# FogCalBoard.net
KiCad netlist of a schematic drawn in Altium Designer
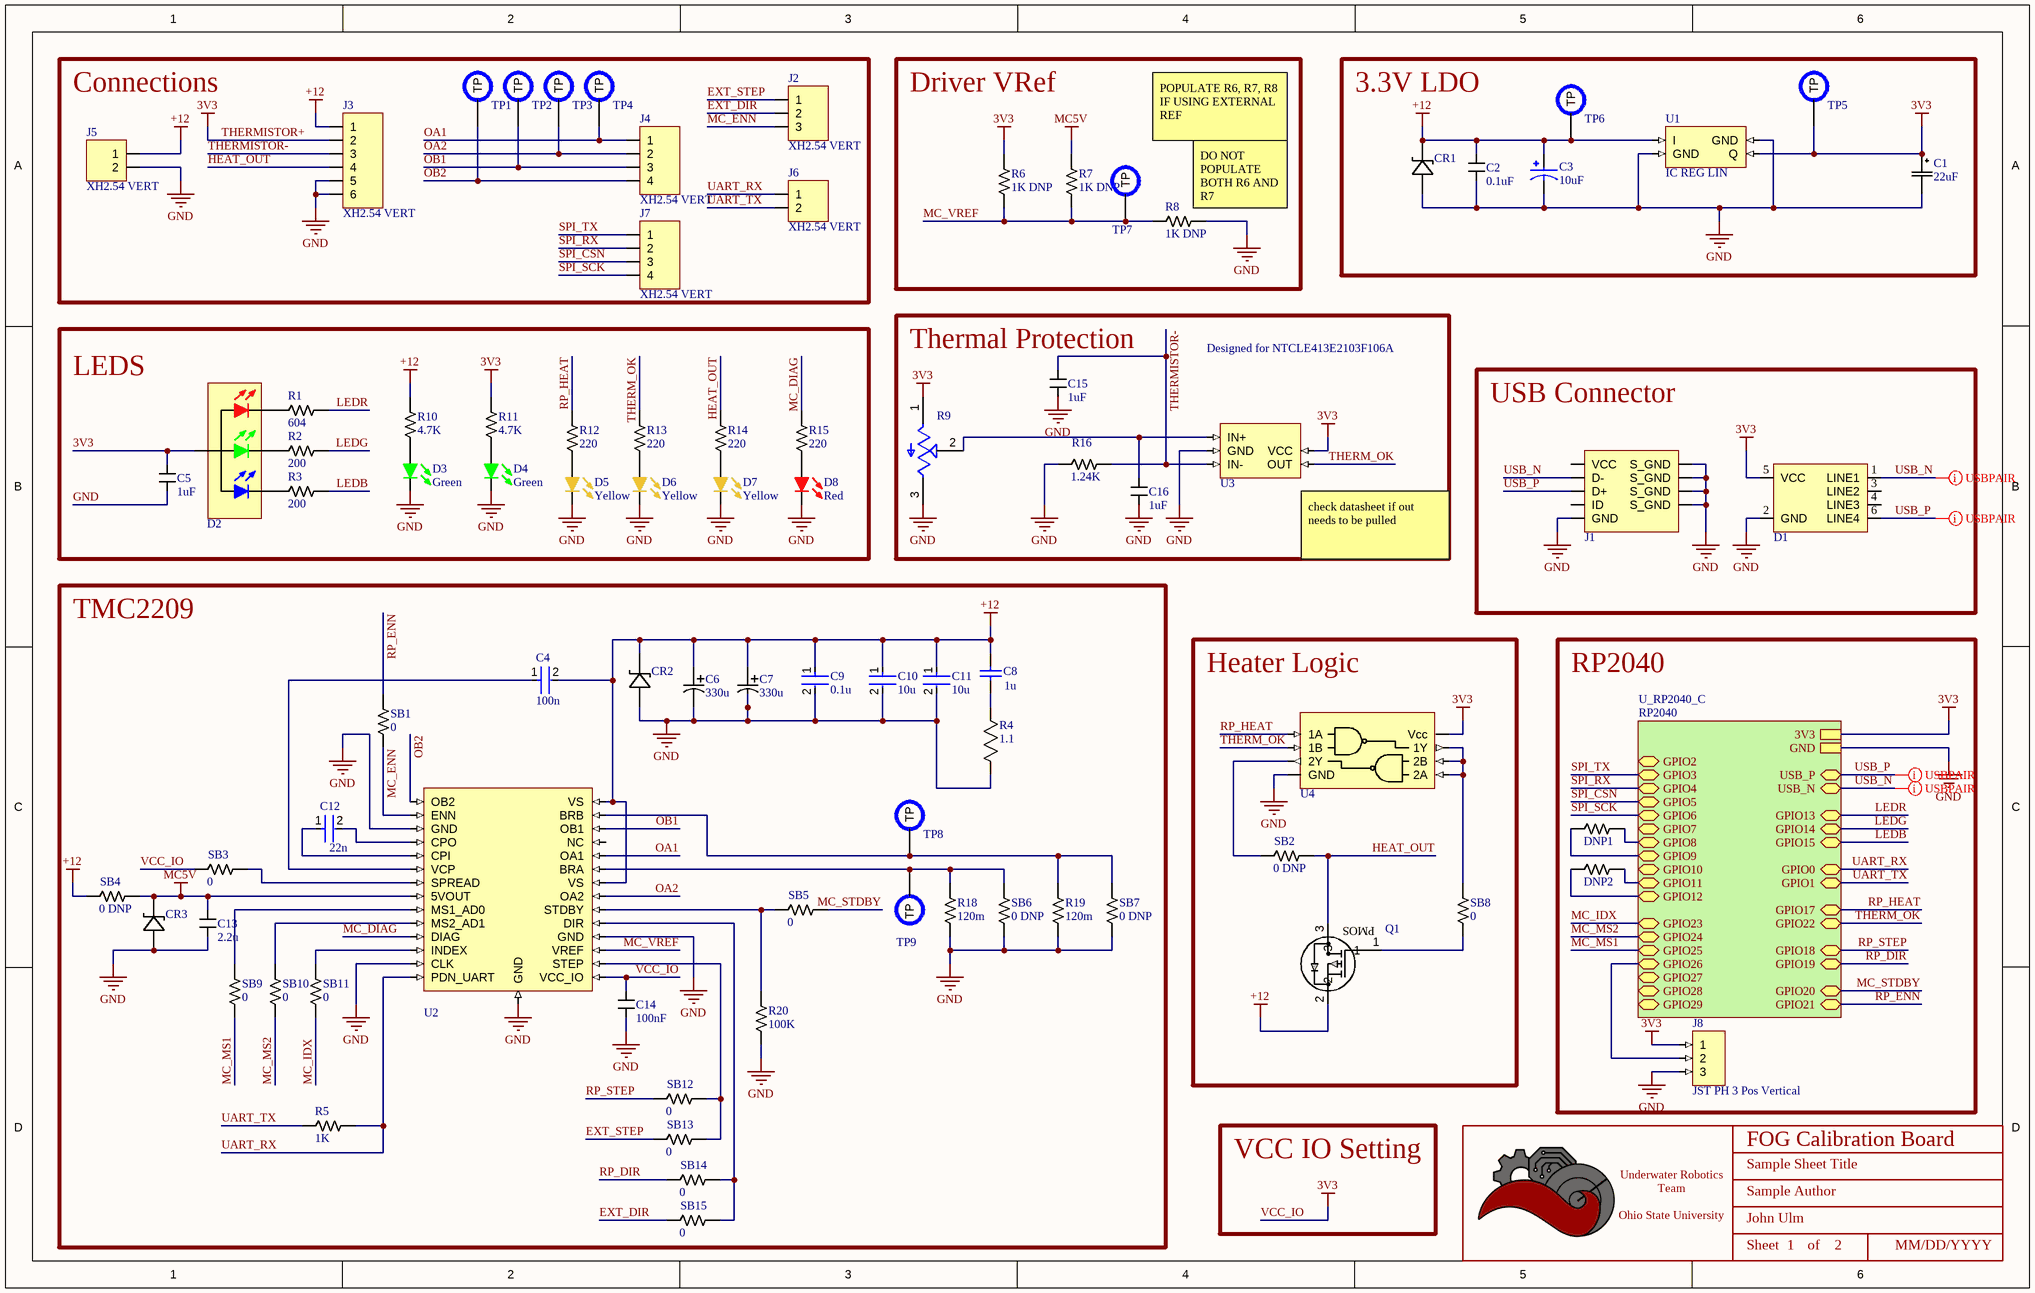
[diagram p0: FogCalBoard.SchDoc]

(export (version "E")
  (design (tool "Eeschema 10.0.6"))
  (components
    (comp (ref "*")
      (value "Title_Block")
      (footprint "LOGO")
      (description "UWRT Schematic Title Block Template\r\n\r\nCreated June 2021, Dylan Trainor")
      (libsource (lib "UWRT") (part "Title_Block"))
    )
    (comp (ref "C1")
      (value "22uF")
      (footprint "PCAP_8x5.4-ELECT_NCA")
      (description "22 µF 35 V Aluminum Electrolytic Capacitors Radial, Can - SMD 1000 Hrs")
      (fields
        (field (name "VOLTAGE") "35V")
        (field (name "Comment") "22uF electrolytic 35 V")
        (field (name "MADE BY") "Robert Pafford")
      )
      (libsource (lib "Capacitors") (part "CAP ALUM 22UF 20% 35V SMD"))
    )
    (comp (ref "C2")
      (value "0.1uF")
      (footprint "CAPACITOR_0603")
      (description "Cap 100nF 25V +/-10%\r\nCeramic 0603")
      (fields
        (field (name "TOLERANCE") "+/- 10%")
        (field (name "VOLTAGE") "6.3V")
        (field (name "MADE BY") "Flip B")
      )
      (libsource (lib "Capacitors") (part "CAPACITOR_0.1uF_0603_25V"))
    )
    (comp (ref "C3")
      (value "10uF")
      (footprint "CAP_EEHZC1J100P")
      (description "10 µF 63 V Aluminum - Polymer Capacitors Radial, Can SMD 120mOhm")
      (fields
        (field (name "TOLERANCE") "+/- 20%")
        (field (name "Comment") "10uF electrolytic 63V")
        (field (name "MADE BY") "Robert Pafford")
      )
      (libsource (lib "Capacitors") (part "CAP ALUM 10UF 20% 63V SMD"))
    )
    (comp (ref "C4")
      (value "100n")
      (footprint "FP-CC0603-DA-IPC_A")
      (description "CAP CER 3900PF 50V X7R 0603")
      (fields (field (name "TOLERANCE") "5%"))
      (libsource (lib "Altium Content Vault") (part "b4654b650e69147ec39a6b967a45e02"))
    )
    (comp (ref "C5")
      (value "1uF")
      (footprint "CAPACITOR_0402")
      (description "Cap 1uF 16V +/-10%\r\nCeramic 0402")
      (fields
        (field (name "TOLERANCE") "+/- 10%")
        (field (name "VOLTAGE") "16V")
        (field (name "MADE BY") "Robert Pafford")
      )
      (libsource (lib "Capacitors") (part "CAPACITOR_1uF_0402"))
    )
    (comp (ref "C6")
      (value "330u")
      (footprint "CAP_EEE-FT1H331AP")
      (description "330 µF 50 V Aluminum Electrolytic Capacitors Radial, Can - SMD 120mOhm @ 100kHz 2000 Hrs @ 105°C")
      (fields (field (name "Comment") "EEE-FT1H331AP"))
      (libsource (lib "Capacitors") (part "CAP ALUM 330UF 20% 50V SMD"))
    )
    (comp (ref "C7")
      (value "330u")
      (footprint "CAP_EEE-FT1H331AP")
      (description "330 µF 50 V Aluminum Electrolytic Capacitors Radial, Can - SMD 120mOhm @ 100kHz 2000 Hrs @ 105°C")
      (fields (field (name "Comment") "EEE-FT1H331AP"))
      (libsource (lib "Capacitors") (part "CAP ALUM 330UF 20% 50V SMD"))
    )
    (comp (ref "C8")
      (value "1u")
      (footprint "CAPC1210(3225)220_N")
      (description "CAP 1uF 50V ±10% 1210 (3225 Metric) Thickness 2.2mm SMD")
      (fields (field (name "TOLERANCE") "Â±10%"))
      (libsource (lib "Altium Content Vault") (part "CAP"))
    )
    (comp (ref "C9")
      (value "0.1u")
      (footprint "FP-CC0603-DA-MFG")
      (description "CAP CER 0.1UF 50V X7R 0603")
      (fields (field (name "MANUFACTURER") "YAGEO") (field (name "VOLTAGE") "50 V"))
      (libsource (lib "Altium Content Vault") (part "11868f565c42a9108669ba33697ecf6"))
    )
    (comp (ref "C10")
      (value "10u")
      (footprint "FP-2220-L_5_7_0_5-W_5_0_4-IPC_A")
      (description "General Purpose Ceramic Capacitor, 2220, 10uF, 10%, X7R, 15%, 50V")
      (fields (field (name "TOLERANCE") "10%") (field (name "VOLTAGE") "50V"))
      (libsource (lib "Altium Content Vault") (part "02cd4be3c70576c341d710602a673aa"))
    )
    (comp (ref "C11")
      (value "10u")
      (footprint "FP-2220-L_5_7_0_5-W_5_0_4-IPC_A")
      (description "General Purpose Ceramic Capacitor, 2220, 10uF, 10%, X7R, 15%, 50V")
      (fields (field (name "TOLERANCE") "10%") (field (name "VOLTAGE") "50V"))
      (libsource (lib "Altium Content Vault") (part "02cd4be3c70576c341d710602a673aa"))
    )
    (comp (ref "C12")
      (value "22n")
      (footprint "FP-C0805C-DN-MFG")
      (description "CAP CER 0.022UF 50V C0G/NP0 0805")
      (fields
        (field (name "OCTOPART") "https://octopart.com/c0805c223j5gactu-kemet-9145108")
        (field (name "MANUFACTURER PART NUMBER") "C0805C223J5GACTU")
      )
      (libsource (lib "Altium Content Vault") (part "b4654b650e69147ec39a6b967a45e02"))
    )
    (comp (ref "C13")
      (value "2.2u")
      (footprint "CAPACITOR_0603")
      (description "2.2 µF ±10% 50V Ceramic Capacitor X5R 0603 (1608 Metric)")
      (fields (field (name "Comment") "GRT188R61H225KE13D"))
      (libsource (lib "Capacitors") (part "CAP CER 2.2UF 50V X5R 0603"))
    )
    (comp (ref "C14")
      (value "CC0603KRX7R9B1B10")
      (footprint "CAPACITOR_0603")
      (fields
        (field (name "MANUFACTURER") "Yageo")
        (field (name "MANUFACTURER PART NUMBER") "CC0603KRX7R9BB104")
        (field (name "CAPACITANCE") "100nF")
      )
      (libsource (lib "Capacitors") (part "CAP CER 100n 50V 0603"))
    )
    (comp (ref "C15")
      (value "1uF")
      (footprint "CAPACITOR_0603")
      (description "Cap 1uF 16V +/-10%\r\nCeramic 0603")
      (fields
        (field (name "TOLERANCE") "+/- 10%")
        (field (name "VOLTAGE") "16V")
        (field (name "MADE BY") "Flip B")
      )
      (libsource (lib "Capacitors") (part "CAPACITOR_1uF_0603"))
    )
    (comp (ref "C16")
      (value "1uF")
      (footprint "CAPACITOR_0603")
      (description "Cap 1uF 16V +/-10%\r\nCeramic 0603")
      (fields
        (field (name "TOLERANCE") "+/- 10%")
        (field (name "VOLTAGE") "16V")
        (field (name "MADE BY") "Flip B")
      )
      (libsource (lib "Capacitors") (part "CAPACITOR_1uF_0603"))
    )
    (comp (ref "CR1")
      (value "SMAJP4KE18A-TP")
      (footprint "DO-214AC")
      (description "TVS DIODE 15.3VWM 25.5VC DO214AC")
      (fields (field (name "COPYRIGHT") "Copyright (C) 2023 Ultra Librarian. All rights reserved."))
      (libsource (lib "Diodes") (part "TVS_Diode_25.5V_16.1A"))
    )
    (comp (ref "CR2")
      (value "SMAJP4KE18A-TP")
      (footprint "DO-214AC")
      (description "TVS DIODE 15.3VWM 25.5VC DO214AC")
      (fields (field (name "COPYRIGHT") "Copyright (C) 2023 Ultra Librarian. All rights reserved."))
      (libsource (lib "Diodes") (part "TVS_Diode_25.5V_16.1A"))
    )
    (comp (ref "CR3")
      (value "SMBJ5.0A")
      (footprint "DO-214AA")
      (description "9.2V Clamp 65.22A Ipp Tvs Diode Surface Mount SMB")
      (libsource (lib "Diodes") (part "TVS DIODE 5VWM 9.2VC SMB"))
    )
    (comp (ref "D1")
      (value "TVS DIODE 5VWM 25VC SOT23-6")
      (footprint "SOT 23-6L")
      (description "25V Clamp 6A (8/20µs) Ipp Tvs Diode Surface Mount SOT-23-6")
      (fields (field (name "MADE BY") "Robert Pafford"))
      (libsource (lib "Diodes") (part "RCLAMP0504S.TCT"))
    )
    (comp (ref "D2")
      (value "EAST1616RGBB4")
      (footprint "LED_0606_4SMD")
      (description "LED RGB CLEAR 4SMD")
      (fields (field (name "MADE BY") "Robert Pafford"))
      (libsource (lib "Diodes") (part "LED_RGB_4SMD"))
    )
    (comp (ref "D3")
      (value "IN-S63AT5G")
      (footprint "LED_0603")
      (description "LED Green Vf= 3V If = 0.005A\r\nIN-S63AT5G")
      (fields (field (name "COLOR") "Green") (field (name "MADE BY") "Robert Pafford"))
      (libsource (lib "Diodes") (part "LED_Green_0603_3V"))
    )
    (comp (ref "D4")
      (value "IN-S63AT5G")
      (footprint "LED_0603")
      (description "LED Green Vf= 3V If = 0.005A\r\nIN-S63AT5G")
      (fields (field (name "COLOR") "Green") (field (name "MADE BY") "Robert Pafford"))
      (libsource (lib "Diodes") (part "LED_Green_0603_3V"))
    )
    (comp (ref "D5")
      (value "150060YS75000")
      (footprint "LED_0603")
      (description "LED Yellow Vf= 2V If = 0.020A\r\n150060YS75000")
      (fields (field (name "COLOR") "Yellow") (field (name "MADE BY") "Robert Pafford"))
      (libsource (lib "Diodes") (part "LED_Yellow_0603"))
    )
    (comp (ref "D6")
      (value "150060YS75000")
      (footprint "LED_0603")
      (description "LED Yellow Vf= 2V If = 0.020A\r\n150060YS75000")
      (fields (field (name "COLOR") "Yellow") (field (name "MADE BY") "Robert Pafford"))
      (libsource (lib "Diodes") (part "LED_Yellow_0603"))
    )
    (comp (ref "D7")
      (value "150060YS75000")
      (footprint "LED_0603")
      (description "LED Yellow Vf= 2V If = 0.020A\r\n150060YS75000")
      (fields (field (name "COLOR") "Yellow") (field (name "MADE BY") "Robert Pafford"))
      (libsource (lib "Diodes") (part "LED_Yellow_0603"))
    )
    (comp (ref "D8")
      (value "150060RS75000")
      (footprint "LED_0603")
      (description "LED Red Vf= 2V If = 0.020A\r\n150060RS75000")
      (fields (field (name "COLOR") "Red") (field (name "MADE BY") "Robert Pafford"))
      (libsource (lib "Diodes") (part "LED_Red_0603"))
    )
    (comp (ref "DNP1")
      (value "DNP")
      (footprint "RESISTOR_0402")
      (description "Do Not Populate 0402")
      (libsource (lib "Resistors") (part "DNP_0402"))
    )
    (comp (ref "DNP2")
      (value "DNP")
      (footprint "RESISTOR_0402")
      (description "Do Not Populate 0402")
      (libsource (lib "Resistors") (part "DNP_0402"))
    )
    (comp (ref "J1")
      (value "USB_MICRO R/A")
      (footprint "CONN_MINIUSB")
      (description "Amphenol Micro USB-B\r\nUSB2.0 5 Pin Right Angle SMD")
      (fields (field (name "MANUFACTURER") "Amphenol") (field (name "CREATED BY") "Flip B"))
      (libsource (lib "Connectors") (part "CONN_MICROUSB"))
    )
    (comp (ref "J2")
      (value "XH2.54 VERT")
      (footprint "CONN_JST_XH254_3POS_VERT")
      (description "JST XH 2.54mm Pitch 3 Pos Vertical")
      (fields (field (name "MANUFACTURER") "JST") (field (name "CREATED BY") "Robert P"))
      (libsource (lib "Connectors") (part "CONN_JST_XH254_3POS_VERT"))
    )
    (comp (ref "J3")
      (value "XH2.54 VERT")
      (footprint "CONN_JST_XH254_6POS_VERT")
      (description "JST XH 2.54mm Pitch 6 Pos Vertical")
      (fields (field (name "MANUFACTURER") "JST") (field (name "CREATED BY") "Flip B"))
      (libsource (lib "Connectors") (part "CONN_JST_XH254_6POS_VERT"))
    )
    (comp (ref "J4")
      (value "XH2.54 VERT")
      (footprint "CONN_JST_XH254_4POS_VERT")
      (description "JST XH 2.54mm Pitch 4 Pos Vertical")
      (fields (field (name "MANUFACTURER") "JST") (field (name "CREATED BY") "Robert P"))
      (libsource (lib "Connectors") (part "CONN_JST_XH254_4POS_VERT"))
    )
    (comp (ref "J5")
      (value "XH2.54 VERT")
      (footprint "CONN_JST_XH254_2POS_VERT")
      (description "JST XH 2.54mm Pitch 2 Pos Vertical")
      (fields (field (name "MANUFACTURER") "JST") (field (name "CREATED BY") "Robert P"))
      (libsource (lib "Connectors") (part "CONN_JST_XH254_2POS_VERT"))
    )
    (comp (ref "J6")
      (value "XH2.54 VERT")
      (footprint "CONN_JST_XH254_2POS_VERT")
      (description "JST XH 2.54mm Pitch 2 Pos Vertical")
      (fields (field (name "MANUFACTURER") "JST") (field (name "CREATED BY") "Robert P"))
      (libsource (lib "") (part "CONN_JST_XH254_2POS_VERT_1"))
    )
    (comp (ref "J7")
      (value "XH2.54 VERT")
      (footprint "CONN_JST_XH254_4POS_VERT")
      (description "JST XH 2.54mm Pitch 4 Pos Vertical")
      (fields (field (name "MANUFACTURER") "JST") (field (name "CREATED BY") "Robert P"))
      (libsource (lib "Connectors") (part "CONN_JST_XH254_4POS_VERT"))
    )
    (comp (ref "J8")
      (value "JST PH 3 Pos Vertical")
      (footprint "CONN_JST_PH_3POS_VERT")
      (libsource (lib "Connectors") (part "CONN_JST_PH_3POS_VERT"))
    )
    (comp (ref "Q1")
      (value "MOSFET P-CHANNEL 20V 4.7A SOT23")
      (footprint "SOT-23-3")
      (description "P-Channel 20 V 4.7A (Tc) 1.56W (Tc) Surface Mount SOT-23")
      (fields
        (field (name "MANUFACTURER_PART_NUMBER") "TSM500P02CX")
        (field (name "CREATED BY") "Robert Pafford")
      )
      (libsource (lib "Transistors") (part "TSM500P02CX"))
    )
    (comp (ref "R1")
      (value "604 Ohm 1% 1/16W")
      (footprint "RESISTOR_0402")
      (description "RES 604 OHM 1% 1/16W 0402")
      (fields
        (field (name "TOLERANCE") "+/- 1%")
        (field (name "VALUE  (OHMS)") "604")
        (field (name "MADE BY") "Robert Pafford")
      )
      (libsource (lib "Resistors") (part "RESISTOR_604_0402"))
    )
    (comp (ref "R2")
      (value "200 Ohm 1% 1/16W")
      (footprint "RESISTOR_0402")
      (description "RES 200 OHM 1% 1/16W 0402")
      (fields
        (field (name "TOLERANCE") "+/- 1%")
        (field (name "VALUE  (OHMS)") "200")
        (field (name "MADE BY") "Robert Pafford")
      )
      (libsource (lib "Resistors") (part "RESISTOR_200_0402"))
    )
    (comp (ref "R3")
      (value "200 Ohm 1% 1/16W")
      (footprint "RESISTOR_0402")
      (description "RES 200 OHM 1% 1/16W 0402")
      (fields
        (field (name "TOLERANCE") "+/- 1%")
        (field (name "VALUE  (OHMS)") "200")
        (field (name "MADE BY") "Robert Pafford")
      )
      (libsource (lib "Resistors") (part "RESISTOR_200_0402"))
    )
    (comp (ref "R4")
      (value "1.1")
      (footprint "RESISTOR_0603")
      (description "1.1 Ohms ±1% 0.1W, 1/10W Chip Resistor 0603 (1608 Metric) Automotive AEC-Q200 Thick Film")
      (fields (field (name "Comment") "CRCW06031R10FKEA"))
      (libsource (lib "Resistors") (part "RES SMD 1.1 OHM 1% 1/10W 0603"))
    )
    (comp (ref "R5")
      (value "1K")
      (footprint "RESISTOR_0603")
      (description "1 kOhms ±1% 0.1W, 1/10W Chip Resistor 0603 (1608 Metric) Automotive AEC-Q200 Thick Film")
      (fields (field (name "Comment") "RMCF0603FT1K00"))
      (libsource (lib "Resistors") (part "RES 1K OHM 1% 1/10W 0603"))
    )
    (comp (ref "R6")
      (value "1k Ohm 5% 1/8W")
      (footprint "RESISTOR_0603")
      (description "RES 1k OHM 5% 1/8W 0603")
      (fields
        (field (name "TOLERANCE") "+/- 5%")
        (field (name "VALUE  (OHMS)") "1K DNP")
        (field (name "MADE BY") "Robert Pafford")
      )
      (libsource (lib "Resistors") (part "RESISTOR_1K_0603"))
    )
    (comp (ref "R7")
      (value "1k Ohm 5% 1/8W")
      (footprint "RESISTOR_0603")
      (description "RES 1k OHM 5% 1/8W 0603")
      (fields
        (field (name "TOLERANCE") "+/- 5%")
        (field (name "VALUE  (OHMS)") "1K DNP")
        (field (name "MADE BY") "Robert Pafford")
      )
      (libsource (lib "Resistors") (part "RESISTOR_1K_0603"))
    )
    (comp (ref "R8")
      (value "1k Ohm 5% 1/8W")
      (footprint "RESISTOR_0603")
      (description "RES 1k OHM 5% 1/8W 0603")
      (fields
        (field (name "TOLERANCE") "+/- 5%")
        (field (name "VALUE  (OHMS)") "1K DNP")
        (field (name "MADE BY") "Robert Pafford")
      )
      (libsource (lib "Resistors") (part "RESISTOR_1K_0603"))
    )
    (comp (ref "R9")
      (value "TC33X-2-203E")
      (footprint "TRIM_TC33X-2-203E")
      (description "20 kOhms 0.1W, 1/10W J Lead Surface Mount Trimmer Potentiometer Cermet 1 Turn Top Adjustment")
      (fields (field (name "MF") "Bourns") (field (name "DIGI-KEY_PART_NUMBER") "TC33X-2-203ECT-ND"))
      (libsource (lib "Resistors") (part "TC33X-2-203E"))
    )
    (comp (ref "R10")
      (value "4.7k Ohm 5% 1/10W")
      (footprint "RESISTOR_0603")
      (description "RES 4.7k OHM 5% 1/10W 0603")
      (fields
        (field (name "TOLERANCE") "+/- 5%")
        (field (name "VALUE  (OHMS)") "4.7K")
        (field (name "MADE BY") "Robert Pafford")
      )
      (libsource (lib "Resistors") (part "RESISTOR_4.7K_0603"))
    )
    (comp (ref "R11")
      (value "4.7k Ohm 5% 1/10W")
      (footprint "RESISTOR_0603")
      (description "RES 4.7k OHM 5% 1/10W 0603")
      (fields
        (field (name "TOLERANCE") "+/- 5%")
        (field (name "VALUE  (OHMS)") "4.7K")
        (field (name "MADE BY") "Robert Pafford")
      )
      (libsource (lib "Resistors") (part "RESISTOR_4.7K_0603"))
    )
    (comp (ref "R12")
      (value "220 Ohm 5% 1/8W")
      (footprint "RESISTOR_0603")
      (description "RES 220 OHM 5% 1/8W 0603")
      (fields
        (field (name "TOLERANCE") "+/- 5%")
        (field (name "VALUE  (OHMS)") "220")
        (field (name "MADE BY") "John S")
      )
      (libsource (lib "Resistors") (part "RESISTOR_200_0603"))
    )
    (comp (ref "R13")
      (value "220 Ohm 5% 1/8W")
      (footprint "RESISTOR_0603")
      (description "RES 220 OHM 5% 1/8W 0603")
      (fields
        (field (name "TOLERANCE") "+/- 5%")
        (field (name "VALUE  (OHMS)") "220")
        (field (name "MADE BY") "John S")
      )
      (libsource (lib "Resistors") (part "RESISTOR_200_0603"))
    )
    (comp (ref "R14")
      (value "220 Ohm 5% 1/8W")
      (footprint "RESISTOR_0603")
      (description "RES 220 OHM 5% 1/8W 0603")
      (fields
        (field (name "TOLERANCE") "+/- 5%")
        (field (name "VALUE  (OHMS)") "220")
        (field (name "MADE BY") "John S")
      )
      (libsource (lib "Resistors") (part "RESISTOR_200_0603"))
    )
    (comp (ref "R15")
      (value "220 Ohm 5% 1/8W")
      (footprint "RESISTOR_0603")
      (description "RES 220 OHM 5% 1/8W 0603")
      (fields
        (field (name "TOLERANCE") "+/- 5%")
        (field (name "VALUE  (OHMS)") "220")
        (field (name "MADE BY") "John S")
      )
      (libsource (lib "Resistors") (part "RESISTOR_200_0603"))
    )
    (comp (ref "R16")
      (value "RES 1.24K OHM 1% 1/10W 0603")
      (footprint "RESISTOR_0603")
      (description "1.24 kOhms ±1% 0.1W, 1/10W Chip Resistor 0603 (1608 Metric) Automotive AEC-Q200 Thick Film")
      (fields
        (field (name "TOLERANCE") "+/- 1%")
        (field (name "VALUE (OHMS)") "1.24K")
        (field (name "CREATED BY") "John Ulm")
        (field (name "VERIFIED BY") "*")
      )
      (libsource (lib "Resistors") (part "RESISTOR_1.24K_1%_0603"))
    )
    (comp (ref "R18")
      (value "120m")
      (footprint "RESISTOR_1210")
      (fields (field (name "Comment") "RCWE1210R120FKEA"))
      (libsource (lib "Resistors") (part "RES 0.12 OHM 1% 1W 1210"))
    )
    (comp (ref "R19")
      (value "120m")
      (footprint "RESISTOR_1210")
      (fields (field (name "Comment") "RCWE1210R120FKEA"))
      (libsource (lib "Resistors") (part "RES 0.12 OHM 1% 1W 1210"))
    )
    (comp (ref "R20")
      (value "100k Ohm 5% 1/8W")
      (footprint "RESISTOR_0603")
      (description "RES 100k OHM 5% 1/10W 0603")
      (fields
        (field (name "TOLERANCE") "+/- 5%")
        (field (name "VALUE  (OHMS)") "100K")
        (field (name "MADE BY") "Flip B")
      )
      (libsource (lib "Resistors") (part "RESISTOR_100K_0603"))
    )
    (comp (ref "SB1")
      (value "0 Ohm Jumper No Fit")
      (footprint "RESISTOR_0603")
      (description "0 Ohm Jumper No Fit for Solder Bridge")
      (fields (field (name "VALUE  (OHMS)") "0") (field (name "MADE BY") "Robert Pafford"))
      (libsource (lib "Resistors") (part "JUMPER_0_0603"))
    )
    (comp (ref "SB2")
      (value "0 Ohm Jumper No Fit")
      (footprint "RESISTOR_0603")
      (description "0 Ohm Jumper No Fit for Solder Bridge")
      (fields (field (name "VALUE  (OHMS)") "0 DNP") (field (name "MADE BY") "Robert Pafford"))
      (libsource (lib "Resistors") (part "JUMPER_0_0603"))
    )
    (comp (ref "SB3")
      (value "0 Ohm Jumper No Fit")
      (footprint "RESISTOR_0603")
      (description "0 Ohm Jumper No Fit for Solder Bridge")
      (fields (field (name "VALUE  (OHMS)") "0") (field (name "MADE BY") "Robert Pafford"))
      (libsource (lib "Resistors") (part "JUMPER_0_0603"))
    )
    (comp (ref "SB4")
      (value "0 Ohm Jumper No Fit")
      (footprint "RESISTOR_0603")
      (description "0 Ohm Jumper No Fit for Solder Bridge")
      (fields (field (name "VALUE  (OHMS)") "0 DNP") (field (name "MADE BY") "Robert Pafford"))
      (libsource (lib "Resistors") (part "JUMPER_0_0603"))
    )
    (comp (ref "SB5")
      (value "0 Ohm Jumper No Fit")
      (footprint "RESISTOR_0603")
      (description "0 Ohm Jumper No Fit for Solder Bridge")
      (fields (field (name "VALUE  (OHMS)") "0") (field (name "MADE BY") "Robert Pafford"))
      (libsource (lib "Resistors") (part "JUMPER_0_0603"))
    )
    (comp (ref "SB6")
      (value "0 Ohm Jumper No Fit")
      (footprint "RESISTOR_0603")
      (description "0 Ohm Jumper No Fit for Solder Bridge")
      (fields (field (name "VALUE  (OHMS)") "0 DNP") (field (name "MADE BY") "Robert Pafford"))
      (libsource (lib "Resistors") (part "JUMPER_0_0603"))
    )
    (comp (ref "SB7")
      (value "0 Ohm Jumper No Fit")
      (footprint "RESISTOR_0603")
      (description "0 Ohm Jumper No Fit for Solder Bridge")
      (fields (field (name "VALUE  (OHMS)") "0 DNP") (field (name "MADE BY") "Robert Pafford"))
      (libsource (lib "Resistors") (part "JUMPER_0_0603"))
    )
    (comp (ref "SB8")
      (value "0 Ohm Jumper No Fit")
      (footprint "RESISTOR_0603")
      (description "0 Ohm Jumper No Fit for Solder Bridge")
      (fields (field (name "VALUE  (OHMS)") "0") (field (name "MADE BY") "Robert Pafford"))
      (libsource (lib "Resistors") (part "JUMPER_0_0603"))
    )
    (comp (ref "SB9")
      (value "0 Ohm Jumper No Fit")
      (footprint "RESISTOR_0603")
      (description "0 Ohm Jumper No Fit for Solder Bridge")
      (fields (field (name "VALUE  (OHMS)") "0") (field (name "MADE BY") "Robert Pafford"))
      (libsource (lib "Resistors") (part "JUMPER_0_0603"))
    )
    (comp (ref "SB10")
      (value "0 Ohm Jumper No Fit")
      (footprint "RESISTOR_0603")
      (description "0 Ohm Jumper No Fit for Solder Bridge")
      (fields (field (name "VALUE  (OHMS)") "0") (field (name "MADE BY") "Robert Pafford"))
      (libsource (lib "Resistors") (part "JUMPER_0_0603"))
    )
    (comp (ref "SB11")
      (value "0 Ohm Jumper No Fit")
      (footprint "RESISTOR_0603")
      (description "0 Ohm Jumper No Fit for Solder Bridge")
      (fields (field (name "VALUE  (OHMS)") "0") (field (name "MADE BY") "Robert Pafford"))
      (libsource (lib "Resistors") (part "JUMPER_0_0603"))
    )
    (comp (ref "SB12")
      (value "0 Ohm Jumper No Fit")
      (footprint "RESISTOR_0603")
      (description "0 Ohm Jumper No Fit for Solder Bridge")
      (fields (field (name "VALUE  (OHMS)") "0") (field (name "MADE BY") "Robert Pafford"))
      (libsource (lib "Resistors") (part "JUMPER_0_0603"))
    )
    (comp (ref "SB13")
      (value "0 Ohm Jumper No Fit")
      (footprint "RESISTOR_0603")
      (description "0 Ohm Jumper No Fit for Solder Bridge")
      (fields (field (name "VALUE  (OHMS)") "0") (field (name "MADE BY") "Robert Pafford"))
      (libsource (lib "Resistors") (part "JUMPER_0_0603"))
    )
    (comp (ref "SB14")
      (value "0 Ohm Jumper No Fit")
      (footprint "RESISTOR_0603")
      (description "0 Ohm Jumper No Fit for Solder Bridge")
      (fields (field (name "VALUE  (OHMS)") "0") (field (name "MADE BY") "Robert Pafford"))
      (libsource (lib "Resistors") (part "JUMPER_0_0603"))
    )
    (comp (ref "SB15")
      (value "0 Ohm Jumper No Fit")
      (footprint "RESISTOR_0603")
      (description "0 Ohm Jumper No Fit for Solder Bridge")
      (fields (field (name "VALUE  (OHMS)") "0") (field (name "MADE BY") "Robert Pafford"))
      (libsource (lib "Resistors") (part "JUMPER_0_0603"))
    )
    (comp (ref "TP1")
      (value "PCB Test Point")
      (footprint "TESTPOINT_1.2MM")
      (fields (field (name "MADE BY") "Robert Pafford"))
      (libsource (lib "Connectors") (part "TESTPOINT"))
    )
    (comp (ref "TP2")
      (value "PCB Test Point")
      (footprint "TESTPOINT_1.2MM")
      (fields (field (name "MADE BY") "Robert Pafford"))
      (libsource (lib "Connectors") (part "TESTPOINT"))
    )
    (comp (ref "TP3")
      (value "PCB Test Point")
      (footprint "TESTPOINT_1.2MM")
      (fields (field (name "MADE BY") "Robert Pafford"))
      (libsource (lib "Connectors") (part "TESTPOINT"))
    )
    (comp (ref "TP4")
      (value "PCB Test Point")
      (footprint "TESTPOINT_1.2MM")
      (fields (field (name "MADE BY") "Robert Pafford"))
      (libsource (lib "Connectors") (part "TESTPOINT"))
    )
    (comp (ref "TP5")
      (value "PCB Test Point")
      (footprint "TESTPOINT_1.2MM")
      (fields (field (name "MADE BY") "Robert Pafford"))
      (libsource (lib "Connectors") (part "TESTPOINT"))
    )
    (comp (ref "TP6")
      (value "PCB Test Point")
      (footprint "TESTPOINT_1.2MM")
      (fields (field (name "MADE BY") "Robert Pafford"))
      (libsource (lib "Connectors") (part "TESTPOINT"))
    )
    (comp (ref "TP7")
      (value "PCB Test Point")
      (footprint "TESTPOINT_1.2MM")
      (fields (field (name "MADE BY") "Robert Pafford"))
      (libsource (lib "Connectors") (part "TESTPOINT"))
    )
    (comp (ref "TP8")
      (value "PCB Test Point")
      (footprint "TESTPOINT_1.2MM")
      (fields (field (name "MADE BY") "Robert Pafford"))
      (libsource (lib "Connectors") (part "TESTPOINT"))
    )
    (comp (ref "TP9")
      (value "PCB Test Point")
      (footprint "TESTPOINT_1.2MM")
      (fields (field (name "MADE BY") "Robert Pafford"))
      (libsource (lib "Connectors") (part "TESTPOINT"))
    )
    (comp (ref "U1")
      (value "IC REG LIN")
      (footprint "SOT-223-4")
      (description "Linear Voltage Regulator IC Positive Fixed 1 Output 400mA PG-SOT223-4")
      (libsource (lib "Integrated Circuits") (part "TLE42744GSV33HTMA1"))
    )
    (comp (ref "U2")
      (value "TMC2209-LA-T")
      (footprint "QFN-28")
      (description "Bipolar Motor Driver Power MOSFET Step/Direction, UART 28-QFN (5x5)")
      (libsource (lib "Integrated Circuits") (part "TMC2209-LA-T"))
    )
    (comp (ref "U3")
      (value "IC COMPARATOR 1 GEN PUR SC70-5")
      (footprint "SOT-353")
      (description "Comparator General Purpose Open-Collector SC-70-5")
      (libsource (lib "Integrated Circuits") (part "LMV331IDCKR"))
    )
    (comp (ref "U4")
      (value "IC GATE NAND SCHMITT 2CH 2IN SM8")
      (footprint "MSOP-8_PI4ULS5V202UEX")
      (description "NAND Gate IC 2 Channel Schmitt Trigger SM8")
      (libsource (lib "Integrated Circuits") (part "SN74LVC2G132DCTR"))
    )
  )
  (nets
    (net (code "1") (name "+12") (class "Default")
      (node (ref "C10") (pin "1") (pinfunction "1_1") (pintype "passive"))
      (node (ref "C11") (pin "1") (pinfunction "1_1") (pintype "passive"))
      (node (ref "C2") (pin "2") (pinfunction "2_2") (pintype "passive"))
      (node (ref "C3") (pin "1") (pinfunction "1_1") (pintype "passive"))
      (node (ref "C4") (pin "2") (pinfunction "2_2") (pintype "passive"))
      (node (ref "C6") (pin "1") (pinfunction "1_1") (pintype "passive"))
      (node (ref "C7") (pin "1") (pinfunction "1_1") (pintype "passive"))
      (node (ref "C8") (pin "2") (pinfunction "2_2") (pintype "passive"))
      (node (ref "C9") (pin "1") (pinfunction "1_1") (pintype "passive"))
      (node (ref "CR1") (pin "1") (pinfunction "ANODE_1") (pintype "passive"))
      (node (ref "CR2") (pin "1") (pinfunction "ANODE_1") (pintype "passive"))
      (node (ref "J3") (pin "1") (pinfunction "1_1") (pintype "passive"))
      (node (ref "J5") (pin "1") (pinfunction "1_1") (pintype "passive"))
      (node (ref "Q1") (pin "2") (pinfunction "2_2") (pintype "passive"))
      (node (ref "R10") (pin "1") (pinfunction "1_1") (pintype "passive"))
      (node (ref "SB4") (pin "2") (pinfunction "2_2") (pintype "passive"))
      (node (ref "TP6") (pin "TP") (pinfunction "TP_TP") (pintype "passive"))
      (node (ref "U1") (pin "1") (pinfunction "I_1") (pintype "input"))
      (node (ref "U2") (pin "22") (pinfunction "VS_22") (pintype "input"))
      (node (ref "U2") (pin "28") (pinfunction "VS_28") (pintype "input"))
    )
    (net (code "2") (name "/EXT_DIR") (class "Default")
      (node (ref "J2") (pin "2") (pinfunction "2_2") (pintype "passive"))
      (node (ref "SB15") (pin "2") (pinfunction "2_2") (pintype "passive"))
    )
    (net (code "3") (name "/EXT_STEP") (class "Default")
      (node (ref "J2") (pin "1") (pinfunction "1_1") (pintype "passive"))
      (node (ref "SB13") (pin "2") (pinfunction "2_2") (pintype "passive"))
    )
    (net (code "6") (name "/GPIO8") (class "Default")
      (node (ref "DNP1") (pin "1") (pinfunction "1_1") (pintype "passive"))
    )
    (net (code "7") (name "/GPIO9") (class "Default")
      (node (ref "DNP1") (pin "2") (pinfunction "2_2") (pintype "passive"))
    )
    (net (code "9") (name "/GPIO11") (class "Default")
      (node (ref "DNP2") (pin "1") (pinfunction "1_1") (pintype "passive"))
    )
    (net (code "10") (name "/GPIO12") (class "Default")
      (node (ref "DNP2") (pin "2") (pinfunction "2_2") (pintype "passive"))
    )
    (net (code "11") (name "/GPIO26") (class "Default")
      (node (ref "J8") (pin "2") (pinfunction "2_2") (pintype "input"))
    )
    (net (code "15") (name "/HEAT_OUT") (class "Default")
      (node (ref "J3") (pin "4") (pinfunction "4_4") (pintype "passive"))
      (node (ref "Q1") (pin "3") (pinfunction "3_3") (pintype "passive"))
      (node (ref "R14") (pin "1") (pinfunction "1_1") (pintype "passive"))
      (node (ref "SB2") (pin "1") (pinfunction "1_1") (pintype "passive"))
    )
    (net (code "16") (name "/LEDB") (class "Default")
      (node (ref "R3") (pin "1") (pinfunction "1_1") (pintype "passive"))
    )
    (net (code "17") (name "/LEDG") (class "Default")
      (node (ref "R2") (pin "1") (pinfunction "1_1") (pintype "passive"))
    )
    (net (code "18") (name "/LEDR") (class "Default")
      (node (ref "R1") (pin "1") (pinfunction "1_1") (pintype "passive"))
    )
    (net (code "19") (name "/MC_DIAG") (class "Default")
      (node (ref "R15") (pin "1") (pinfunction "1_1") (pintype "passive"))
      (node (ref "U2") (pin "11") (pinfunction "DIAG_11") (pintype "input"))
    )
    (net (code "20") (name "/MC_ENN") (class "Default")
      (node (ref "J2") (pin "3") (pinfunction "3_3") (pintype "passive"))
      (node (ref "SB1") (pin "2") (pinfunction "2_2") (pintype "passive"))
      (node (ref "U2") (pin "2") (pinfunction "ENN_2") (pintype "input"))
    )
    (net (code "21") (name "/MC_IDX") (class "Default")
      (node (ref "SB11") (pin "2") (pinfunction "2_2") (pintype "passive"))
    )
    (net (code "22") (name "/MC_MS1") (class "Default")
      (node (ref "SB9") (pin "2") (pinfunction "2_2") (pintype "passive"))
    )
    (net (code "23") (name "/MC_MS2") (class "Default")
      (node (ref "SB10") (pin "2") (pinfunction "2_2") (pintype "passive"))
    )
    (net (code "24") (name "/MC_STDBY") (class "Default")
      (node (ref "SB5") (pin "1") (pinfunction "1_1") (pintype "passive"))
    )
    (net (code "25") (name "/MC_VREF") (class "Default")
      (node (ref "R6") (pin "2") (pinfunction "2_2") (pintype "passive"))
      (node (ref "R7") (pin "2") (pinfunction "2_2") (pintype "passive"))
      (node (ref "R8") (pin "2") (pinfunction "2_2") (pintype "passive"))
      (node (ref "TP7") (pin "TP") (pinfunction "TP_TP") (pintype "passive"))
      (node (ref "U2") (pin "17") (pinfunction "VREF_17") (pintype "input"))
    )
    (net (code "26") (name "/OA1") (class "Default")
      (node (ref "J4") (pin "1") (pinfunction "1_1") (pintype "passive"))
      (node (ref "TP4") (pin "TP") (pinfunction "TP_TP") (pintype "passive"))
      (node (ref "U2") (pin "24") (pinfunction "OA1_24") (pintype "input"))
    )
    (net (code "27") (name "/OA2") (class "Default")
      (node (ref "J4") (pin "2") (pinfunction "2_2") (pintype "passive"))
      (node (ref "TP3") (pin "TP") (pinfunction "TP_TP") (pintype "passive"))
      (node (ref "U2") (pin "21") (pinfunction "OA2_21") (pintype "input"))
    )
    (net (code "28") (name "/OB1") (class "Default")
      (node (ref "J4") (pin "3") (pinfunction "3_3") (pintype "passive"))
      (node (ref "TP2") (pin "TP") (pinfunction "TP_TP") (pintype "passive"))
      (node (ref "U2") (pin "26") (pinfunction "OB1_26") (pintype "input"))
    )
    (net (code "29") (name "/OB2") (class "Default")
      (node (ref "J4") (pin "4") (pinfunction "4_4") (pintype "passive"))
      (node (ref "TP1") (pin "TP") (pinfunction "TP_TP") (pintype "passive"))
      (node (ref "U2") (pin "1") (pinfunction "OB2_1") (pintype "input"))
    )
    (net (code "30") (name "/RP_DIR") (class "Default")
      (node (ref "SB14") (pin "2") (pinfunction "2_2") (pintype "passive"))
    )
    (net (code "31") (name "/RP_ENN") (class "Default")
      (node (ref "SB1") (pin "1") (pinfunction "1_1") (pintype "passive"))
    )
    (net (code "32") (name "/RP_HEAT") (class "Default")
      (node (ref "R12") (pin "1") (pinfunction "1_1") (pintype "passive"))
      (node (ref "U4") (pin "1") (pinfunction "1A_1") (pintype "input"))
    )
    (net (code "33") (name "/RP_STEP") (class "Default")
      (node (ref "SB12") (pin "2") (pinfunction "2_2") (pintype "passive"))
    )
    (net (code "34") (name "/SPI_CSN") (class "Default")
      (node (ref "J7") (pin "3") (pinfunction "3_3") (pintype "passive"))
    )
    (net (code "35") (name "/SPI_RX") (class "Default")
      (node (ref "J7") (pin "2") (pinfunction "2_2") (pintype "passive"))
    )
    (net (code "36") (name "/SPI_SCK") (class "Default")
      (node (ref "J7") (pin "4") (pinfunction "4_4") (pintype "passive"))
    )
    (net (code "37") (name "/SPI_TX") (class "Default")
      (node (ref "J7") (pin "1") (pinfunction "1_1") (pintype "passive"))
    )
    (net (code "38") (name "/THERMISTOR-") (class "Default")
      (node (ref "C15") (pin "1") (pinfunction "1_1") (pintype "passive"))
      (node (ref "J3") (pin "3") (pinfunction "3_3") (pintype "passive"))
      (node (ref "R16") (pin "1") (pinfunction "1_1") (pintype "passive"))
      (node (ref "U3") (pin "3") (pinfunction "IN-_3") (pintype "input"))
    )
    (net (code "39") (name "/THERM_OK") (class "Default")
      (node (ref "R13") (pin "1") (pinfunction "1_1") (pintype "passive"))
      (node (ref "U3") (pin "4") (pinfunction "OUT_4") (pintype "input"))
      (node (ref "U4") (pin "2") (pinfunction "1B_2") (pintype "input"))
    )
    (net (code "40") (name "/UART_RX") (class "Default")
      (node (ref "J6") (pin "1") (pinfunction "1_1") (pintype "passive"))
      (node (ref "R5") (pin "1") (pinfunction "1_1") (pintype "passive"))
      (node (ref "U2") (pin "14") (pinfunction "PDN_UART_14") (pintype "input"))
    )
    (net (code "41") (name "/UART_TX") (class "Default")
      (node (ref "J6") (pin "2") (pinfunction "2_2") (pintype "passive"))
      (node (ref "R5") (pin "2") (pinfunction "2_2") (pintype "passive"))
    )
    (net (code "42") (name "/USB_N") (class "Default")
      (node (ref "D1") (pin "1") (pinfunction "LINE1_1") (pintype "passive"))
      (node (ref "J1") (pin "2") (pinfunction "D-_2") (pintype "passive"))
    )
    (net (code "43") (name "/USB_P") (class "Default")
      (node (ref "D1") (pin "6") (pinfunction "LINE4_6") (pintype "passive"))
      (node (ref "J1") (pin "3") (pinfunction "D+_3") (pintype "passive"))
    )
    (net (code "44") (name "3V3") (class "Default")
      (node (ref "C1") (pin "1") (pinfunction "1_1") (pintype "passive"))
      (node (ref "C14") (pin "1") (pinfunction "1_1") (pintype "passive"))
      (node (ref "C5") (pin "1") (pinfunction "1_1") (pintype "passive"))
      (node (ref "D1") (pin "5") (pinfunction "VCC_5") (pintype "power_in"))
      (node (ref "D2") (pin "4") (pinfunction "4_4") (pintype "passive"))
      (node (ref "J3") (pin "2") (pinfunction "2_2") (pintype "passive"))
      (node (ref "J8") (pin "1") (pinfunction "1_1") (pintype "input"))
      (node (ref "R11") (pin "1") (pinfunction "1_1") (pintype "passive"))
      (node (ref "R6") (pin "1") (pinfunction "1_1") (pintype "passive"))
      (node (ref "R9") (pin "1") (pinfunction "CCW_1") (pintype "passive"))
      (node (ref "SB3") (pin "2") (pinfunction "2_2") (pintype "passive"))
      (node (ref "TP5") (pin "TP") (pinfunction "TP_TP") (pintype "passive"))
      (node (ref "U1") (pin "3") (pinfunction "Q_3") (pintype "input"))
      (node (ref "U2") (pin "15") (pinfunction "VCC_IO_15") (pintype "input"))
      (node (ref "U3") (pin "5") (pinfunction "VCC_5") (pintype "input"))
      (node (ref "U4") (pin "8") (pinfunction "Vcc_8") (pintype "power_in"))
    )
    (net (code "45") (name "GND") (class "Default")
      (node (ref "C1") (pin "2") (pinfunction "2_2") (pintype "passive"))
      (node (ref "C10") (pin "2") (pinfunction "2_2") (pintype "passive"))
      (node (ref "C11") (pin "2") (pinfunction "2_2") (pintype "passive"))
      (node (ref "C13") (pin "2") (pinfunction "2_2") (pintype "passive"))
      (node (ref "C14") (pin "2") (pinfunction "2_2") (pintype "passive"))
      (node (ref "C15") (pin "2") (pinfunction "2_2") (pintype "passive"))
      (node (ref "C16") (pin "2") (pinfunction "2_2") (pintype "passive"))
      (node (ref "C2") (pin "1") (pinfunction "1_1") (pintype "passive"))
      (node (ref "C3") (pin "2") (pinfunction "2_2") (pintype "passive"))
      (node (ref "C5") (pin "2") (pinfunction "2_2") (pintype "passive"))
      (node (ref "C6") (pin "2") (pinfunction "2_2") (pintype "passive"))
      (node (ref "C7") (pin "2") (pinfunction "2_2") (pintype "passive"))
      (node (ref "C9") (pin "2") (pinfunction "2_2") (pintype "passive"))
      (node (ref "CR1") (pin "2") (pinfunction "CATHODE_2") (pintype "passive"))
      (node (ref "CR2") (pin "2") (pinfunction "CATHODE_2") (pintype "passive"))
      (node (ref "CR3") (pin "2") (pinfunction "ANODE_2") (pintype "passive"))
      (node (ref "D1") (pin "2") (pinfunction "GND_2") (pintype "power_in"))
      (node (ref "D3") (pin "2") (pinfunction "2_2") (pintype "passive"))
      (node (ref "D4") (pin "2") (pinfunction "2_2") (pintype "passive"))
      (node (ref "D5") (pin "2") (pinfunction "2_2") (pintype "passive"))
      (node (ref "D6") (pin "2") (pinfunction "2_2") (pintype "passive"))
      (node (ref "D7") (pin "2") (pinfunction "2_2") (pintype "passive"))
      (node (ref "D8") (pin "2") (pinfunction "2_2") (pintype "passive"))
      (node (ref "J1") (pin "5") (pinfunction "GND_5") (pintype "passive"))
      (node (ref "J1") (pin "6") (pinfunction "S_GND_6") (pintype "passive"))
      (node (ref "J1") (pin "7") (pinfunction "S_GND_7") (pintype "passive"))
      (node (ref "J1") (pin "8") (pinfunction "S_GND_8") (pintype "passive"))
      (node (ref "J1") (pin "9") (pinfunction "S_GND_9") (pintype "passive"))
      (node (ref "J3") (pin "5") (pinfunction "5_5") (pintype "passive"))
      (node (ref "J3") (pin "6") (pinfunction "6_6") (pintype "passive"))
      (node (ref "J5") (pin "2") (pinfunction "2_2") (pintype "passive"))
      (node (ref "J8") (pin "3") (pinfunction "3_3") (pintype "input"))
      (node (ref "R16") (pin "2") (pinfunction "2_2") (pintype "passive"))
      (node (ref "R18") (pin "2") (pinfunction "2_2") (pintype "passive"))
      (node (ref "R19") (pin "2") (pinfunction "2_2") (pintype "passive"))
      (node (ref "R20") (pin "2") (pinfunction "2_2") (pintype "passive"))
      (node (ref "R4") (pin "1") (pinfunction "1_1") (pintype "passive"))
      (node (ref "R8") (pin "1") (pinfunction "1_1") (pintype "passive"))
      (node (ref "R9") (pin "3") (pinfunction "CW_3") (pintype "passive"))
      (node (ref "SB6") (pin "2") (pinfunction "2_2") (pintype "passive"))
      (node (ref "SB7") (pin "2") (pinfunction "2_2") (pintype "passive"))
      (node (ref "U1") (pin "2") (pinfunction "GND_2") (pintype "input"))
      (node (ref "U1") (pin "4") (pinfunction "GND_4") (pintype "input"))
      (node (ref "U2") (pin "13") (pinfunction "CLK_13") (pintype "input"))
      (node (ref "U2") (pin "18") (pinfunction "GND_18") (pintype "input"))
      (node (ref "U2") (pin "29") (pinfunction "GND_29") (pintype "input"))
      (node (ref "U2") (pin "3") (pinfunction "GND_3") (pintype "input"))
      (node (ref "U3") (pin "2") (pinfunction "GND_2") (pintype "input"))
      (node (ref "U4") (pin "4") (pinfunction "GND_4") (pintype "power_in"))
    )
    (net (code "46") (name "MC5V") (class "Default")
      (node (ref "C13") (pin "1") (pinfunction "1_1") (pintype "passive"))
      (node (ref "CR3") (pin "1") (pinfunction "CATHODE_1") (pintype "passive"))
      (node (ref "R7") (pin "1") (pinfunction "1_1") (pintype "passive"))
      (node (ref "SB4") (pin "1") (pinfunction "1_1") (pintype "passive"))
      (node (ref "U2") (pin "8") (pinfunction "5VOUT_8") (pintype "input"))
    )
    (net (code "47") (name "Net-(C8-Pad1)") (class "Default")
      (node (ref "C8") (pin "1") (pinfunction "1_1") (pintype "passive"))
      (node (ref "R4") (pin "2") (pinfunction "2_2") (pintype "passive"))
    )
    (net (code "48") (name "Net-(D2-32)") (class "Default")
      (node (ref "D2") (pin "3") (pinfunction "32_3") (pintype "passive"))
      (node (ref "R3") (pin "2") (pinfunction "2_2") (pintype "passive"))
    )
    (net (code "49") (name "Net-(D2-Pad1)") (class "Default")
      (node (ref "D2") (pin "1") (pinfunction "1_1") (pintype "passive"))
      (node (ref "R1") (pin "2") (pinfunction "2_2") (pintype "passive"))
    )
    (net (code "50") (name "Net-(D2-Pad2)") (class "Default")
      (node (ref "D2") (pin "2") (pinfunction "2_2") (pintype "passive"))
      (node (ref "R2") (pin "2") (pinfunction "2_2") (pintype "passive"))
    )
    (net (code "51") (name "Net-(D3-Pad1)") (class "Default")
      (node (ref "D3") (pin "1") (pinfunction "1_1") (pintype "passive"))
      (node (ref "R10") (pin "2") (pinfunction "2_2") (pintype "passive"))
    )
    (net (code "52") (name "Net-(D4-Pad1)") (class "Default")
      (node (ref "D4") (pin "1") (pinfunction "1_1") (pintype "passive"))
      (node (ref "R11") (pin "2") (pinfunction "2_2") (pintype "passive"))
    )
    (net (code "53") (name "Net-(D5-Pad1)") (class "Default")
      (node (ref "D5") (pin "1") (pinfunction "1_1") (pintype "passive"))
      (node (ref "R12") (pin "2") (pinfunction "2_2") (pintype "passive"))
    )
    (net (code "54") (name "Net-(D6-Pad1)") (class "Default")
      (node (ref "D6") (pin "1") (pinfunction "1_1") (pintype "passive"))
      (node (ref "R13") (pin "2") (pinfunction "2_2") (pintype "passive"))
    )
    (net (code "55") (name "Net-(D7-Pad1)") (class "Default")
      (node (ref "D7") (pin "1") (pinfunction "1_1") (pintype "passive"))
      (node (ref "R14") (pin "2") (pinfunction "2_2") (pintype "passive"))
    )
    (net (code "56") (name "Net-(D8-Pad1)") (class "Default")
      (node (ref "D8") (pin "1") (pinfunction "1_1") (pintype "passive"))
      (node (ref "R15") (pin "2") (pinfunction "2_2") (pintype "passive"))
    )
    (net (code "57") (name "Net-(Q1-Pad1)") (class "Default")
      (node (ref "Q1") (pin "1") (pinfunction "1_1") (pintype "passive"))
      (node (ref "SB8") (pin "2") (pinfunction "2_2") (pintype "passive"))
    )
    (net (code "58") (name "Net-(R9-W)") (class "Default")
      (node (ref "C16") (pin "1") (pinfunction "1_1") (pintype "passive"))
      (node (ref "R9") (pin "2") (pinfunction "W_2") (pintype "passive"))
      (node (ref "U3") (pin "1") (pinfunction "IN+_1") (pintype "input"))
    )
    (net (code "59") (name "Net-(U2-BRA)") (class "Default")
      (node (ref "R18") (pin "1") (pinfunction "1_1") (pintype "passive"))
      (node (ref "SB6") (pin "1") (pinfunction "1_1") (pintype "passive"))
      (node (ref "TP9") (pin "TP") (pinfunction "TP_TP") (pintype "passive"))
      (node (ref "U2") (pin "23") (pinfunction "BRA_23") (pintype "input"))
    )
    (net (code "60") (name "Net-(U2-BRB)") (class "Default")
      (node (ref "R19") (pin "1") (pinfunction "1_1") (pintype "passive"))
      (node (ref "SB7") (pin "1") (pinfunction "1_1") (pintype "passive"))
      (node (ref "TP8") (pin "TP") (pinfunction "TP_TP") (pintype "passive"))
      (node (ref "U2") (pin "27") (pinfunction "BRB_27") (pintype "input"))
    )
    (net (code "61") (name "Net-(U2-CPI)") (class "Default")
      (node (ref "C12") (pin "1") (pinfunction "1_1") (pintype "passive"))
      (node (ref "U2") (pin "5") (pinfunction "CPI_5") (pintype "input"))
    )
    (net (code "62") (name "Net-(U2-CPO)") (class "Default")
      (node (ref "C12") (pin "2") (pinfunction "2_2") (pintype "passive"))
      (node (ref "U2") (pin "4") (pinfunction "CPO_4") (pintype "input"))
    )
    (net (code "63") (name "Net-(U2-DIR)") (class "Default")
      (node (ref "SB14") (pin "1") (pinfunction "1_1") (pintype "passive"))
      (node (ref "SB15") (pin "1") (pinfunction "1_1") (pintype "passive"))
      (node (ref "U2") (pin "19") (pinfunction "DIR_19") (pintype "input"))
    )
    (net (code "64") (name "Net-(U2-INDEX)") (class "Default")
      (node (ref "SB11") (pin "1") (pinfunction "1_1") (pintype "passive"))
      (node (ref "U2") (pin "12") (pinfunction "INDEX_12") (pintype "input"))
    )
    (net (code "65") (name "Net-(U2-MS1_AD0)") (class "Default")
      (node (ref "SB9") (pin "1") (pinfunction "1_1") (pintype "passive"))
      (node (ref "U2") (pin "9") (pinfunction "MS1_AD0_9") (pintype "input"))
    )
    (net (code "66") (name "Net-(U2-MS2_AD1)") (class "Default")
      (node (ref "SB10") (pin "1") (pinfunction "1_1") (pintype "passive"))
      (node (ref "U2") (pin "10") (pinfunction "MS2_AD1_10") (pintype "input"))
    )
    (net (code "67") (name "Net-(U2-SPREAD)") (class "Default")
      (node (ref "SB3") (pin "1") (pinfunction "1_1") (pintype "passive"))
      (node (ref "U2") (pin "7") (pinfunction "SPREAD_7") (pintype "input"))
    )
    (net (code "68") (name "Net-(U2-STDBY)") (class "Default")
      (node (ref "R20") (pin "1") (pinfunction "1_1") (pintype "passive"))
      (node (ref "SB5") (pin "2") (pinfunction "2_2") (pintype "passive"))
      (node (ref "U2") (pin "20") (pinfunction "STDBY_20") (pintype "input"))
    )
    (net (code "69") (name "Net-(U2-STEP)") (class "Default")
      (node (ref "SB12") (pin "1") (pinfunction "1_1") (pintype "passive"))
      (node (ref "SB13") (pin "1") (pinfunction "1_1") (pintype "passive"))
      (node (ref "U2") (pin "16") (pinfunction "STEP_16") (pintype "input"))
    )
    (net (code "70") (name "Net-(U2-VCP)") (class "Default")
      (node (ref "C4") (pin "1") (pinfunction "1_1") (pintype "passive"))
      (node (ref "U2") (pin "6") (pinfunction "VCP_6") (pintype "input"))
    )
    (net (code "71") (name "Net-(U4-1Y)") (class "Default")
      (node (ref "SB8") (pin "1") (pinfunction "1_1") (pintype "passive"))
      (node (ref "U4") (pin "5") (pinfunction "2A_5") (pintype "input"))
      (node (ref "U4") (pin "6") (pinfunction "2B_6") (pintype "input"))
      (node (ref "U4") (pin "7") (pinfunction "1Y_7") (pintype "output"))
    )
    (net (code "72") (name "Net-(U4-2Y)") (class "Default")
      (node (ref "SB2") (pin "2") (pinfunction "2_2") (pintype "passive"))
      (node (ref "U4") (pin "3") (pinfunction "2Y_3") (pintype "output"))
    )
    (net (code "73") (name "unconnected-(D1-LINE2-Pad3)") (class "Default")
      (node (ref "D1") (pin "3") (pinfunction "LINE2_3") (pintype "passive"))
    )
    (net (code "74") (name "unconnected-(D1-LINE3-Pad4)") (class "Default")
      (node (ref "D1") (pin "4") (pinfunction "LINE3_4") (pintype "passive"))
    )
    (net (code "75") (name "unconnected-(J1-ID-Pad4)") (class "Default")
      (node (ref "J1") (pin "4") (pinfunction "ID_4") (pintype "passive"))
    )
    (net (code "76") (name "unconnected-(J1-VCC-Pad1)") (class "Default")
      (node (ref "J1") (pin "1") (pinfunction "VCC_1") (pintype "passive"))
    )
    (net (code "77") (name "unconnected-(U2-NC-Pad25)") (class "Default")
      (node (ref "U2") (pin "25") (pinfunction "NC_25") (pintype "input"))
    )
  )
)
